# FeatherAzureSphere.net
KiCad netlist of a schematic drawn in EAGLE
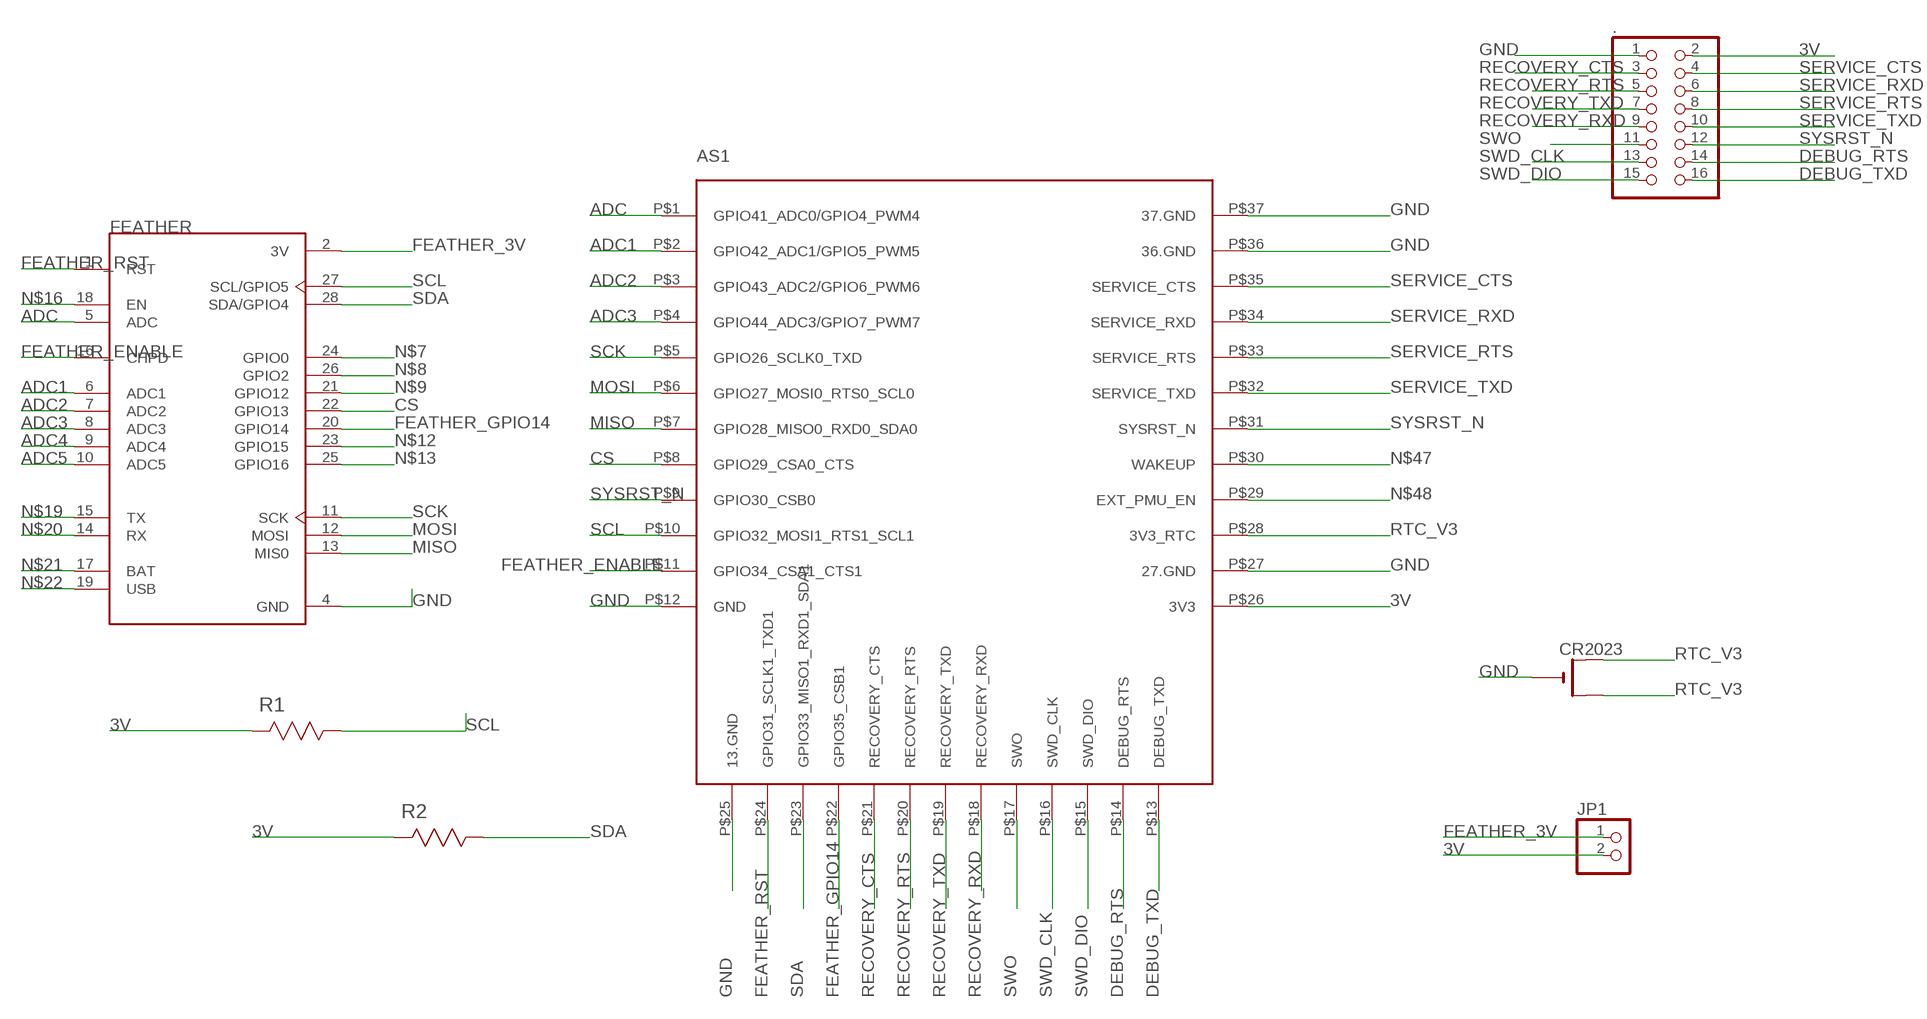
[diagram p0: schematic, sheet 1]

(export (version "E")
  (design (tool "Eeschema 10.0.6"))
  (components
    (comp (ref ".")
      (value "PINHD-2X8")
      (footprint "eagle-import:2X08")
      (libsource (lib "eagle-import") (part "PINHD-2X8"))
    )
    (comp (ref "AS1")
      (value "WF-M620-RSC1")
      (footprint "eagle-import:WF-M620-RSC1")
      (libsource (lib "eagle-import") (part "WF-M620-RSC1"))
    )
    (comp (ref "CR2023")
      (value "CR2032SMT")
      (footprint "eagle-import:CR2032-SMD")
      (libsource (lib "eagle-import") (part "CR2032SMT"))
    )
    (comp (ref "FEATHER")
      (value "2821")
      (footprint "eagle-import:XCVR_2821")
      (fields (field (name "MF") "Adafruit Industries"))
      (libsource (lib "eagle-import") (part "2821"))
    )
    (comp (ref "JP1")
      (value "PINHD-1X2")
      (footprint "eagle-import:1X02")
      (libsource (lib "eagle-import") (part "PINHD-1X2"))
    )
    (comp (ref "R1")
      (value "ERJ-8RQF1R5V")
      (footprint "eagle-import:RESC3216X71N")
      (fields (field (name "TOLERANCE") "±1 %"))
      (libsource (lib "eagle-import") (part "ERJ-8RQF1R5V"))
    )
    (comp (ref "R2")
      (value "ERJ-8RQF1R5V")
      (footprint "eagle-import:RESC3216X71N")
      (fields (field (name "TOLERANCE") "±1 %"))
      (libsource (lib "eagle-import") (part "ERJ-8RQF1R5V"))
    )
  )
  (nets
    (net (code "1") (name "/3V") (class "Default")
      (node (ref ".") (pin "2") (pinfunction "2_2") (pintype "passive"))
      (node (ref "AS1") (pin "P$26") (pinfunction "3V3_P$26") (pintype "bidirectional"))
      (node (ref "JP1") (pin "2") (pinfunction "2_2") (pintype "passive"))
      (node (ref "R1") (pin "2") (pinfunction "R2_2") (pintype "passive"))
      (node (ref "R2") (pin "2") (pinfunction "R2_2") (pintype "passive"))
    )
    (net (code "2") (name "/ADC") (class "Default")
      (node (ref "AS1") (pin "P$1") (pinfunction "GPIO41_ADC0/GPIO4_PWM4_P$1") (pintype "bidirectional"))
      (node (ref "FEATHER") (pin "5") (pinfunction "ADC_5") (pintype "bidirectional"))
    )
    (net (code "3") (name "/ADC1") (class "Default")
      (node (ref "AS1") (pin "P$2") (pinfunction "GPIO42_ADC1/GPIO5_PWM5_P$2") (pintype "bidirectional"))
      (node (ref "FEATHER") (pin "6") (pinfunction "ADC1_6") (pintype "bidirectional"))
    )
    (net (code "4") (name "/ADC2") (class "Default")
      (node (ref "AS1") (pin "P$3") (pinfunction "GPIO43_ADC2/GPIO6_PWM6_P$3") (pintype "bidirectional"))
      (node (ref "FEATHER") (pin "7") (pinfunction "ADC2_7") (pintype "bidirectional"))
    )
    (net (code "5") (name "/ADC3") (class "Default")
      (node (ref "AS1") (pin "P$4") (pinfunction "GPIO44_ADC3/GPIO7_PWM7_P$4") (pintype "bidirectional"))
      (node (ref "FEATHER") (pin "8") (pinfunction "ADC3_8") (pintype "bidirectional"))
    )
    (net (code "6") (name "/ADC4") (class "Default")
      (node (ref "FEATHER") (pin "9") (pinfunction "ADC4_9") (pintype "bidirectional"))
    )
    (net (code "7") (name "/ADC5") (class "Default")
      (node (ref "FEATHER") (pin "10") (pinfunction "ADC5_10") (pintype "bidirectional"))
    )
    (net (code "8") (name "/CS") (class "Default")
      (node (ref "AS1") (pin "P$8") (pinfunction "GPIO29_CSA0_CTS_P$8") (pintype "bidirectional"))
      (node (ref "FEATHER") (pin "22") (pinfunction "GPIO13_22") (pintype "bidirectional"))
    )
    (net (code "9") (name "/DEBUG_RTS") (class "Default")
      (node (ref ".") (pin "14") (pinfunction "14_14") (pintype "passive"))
      (node (ref "AS1") (pin "P$14") (pinfunction "DEBUG_RTS_P$14") (pintype "bidirectional"))
    )
    (net (code "10") (name "/DEBUG_TXD") (class "Default")
      (node (ref ".") (pin "16") (pinfunction "16_16") (pintype "passive"))
      (node (ref "AS1") (pin "P$13") (pinfunction "DEBUG_TXD_P$13") (pintype "bidirectional"))
    )
    (net (code "11") (name "/FEATHER_3V") (class "Default")
      (node (ref "FEATHER") (pin "2") (pinfunction "3V_2") (pintype "power_in"))
      (node (ref "JP1") (pin "1") (pinfunction "1_1") (pintype "passive"))
    )
    (net (code "12") (name "/FEATHER_ENABLE") (class "Default")
      (node (ref "AS1") (pin "P$11") (pinfunction "GPIO34_CSA1_CTS1_P$11") (pintype "bidirectional"))
      (node (ref "FEATHER") (pin "16") (pinfunction "CHPD_16") (pintype "bidirectional"))
    )
    (net (code "13") (name "/FEATHER_GPIO14") (class "Default")
      (node (ref "AS1") (pin "P$22") (pinfunction "GPIO35_CSB1_P$22") (pintype "bidirectional"))
      (node (ref "FEATHER") (pin "20") (pinfunction "GPIO14_20") (pintype "bidirectional"))
    )
    (net (code "14") (name "/FEATHER_RST") (class "Default")
      (node (ref "AS1") (pin "P$24") (pinfunction "GPIO31_SCLK1_TXD1_P$24") (pintype "bidirectional"))
      (node (ref "FEATHER") (pin "1") (pinfunction "RST_1") (pintype "input"))
    )
    (net (code "15") (name "/GND") (class "Default")
      (node (ref ".") (pin "1") (pinfunction "1_1") (pintype "passive"))
      (node (ref "AS1") (pin "P$12") (pinfunction "GND_P$12") (pintype "bidirectional"))
      (node (ref "AS1") (pin "P$25") (pinfunction "13.GND_P$25") (pintype "bidirectional"))
      (node (ref "AS1") (pin "P$27") (pinfunction "27.GND_P$27") (pintype "bidirectional"))
      (node (ref "AS1") (pin "P$36") (pinfunction "36.GND_P$36") (pintype "bidirectional"))
      (node (ref "AS1") (pin "P$37") (pinfunction "37.GND_P$37") (pintype "bidirectional"))
      (node (ref "CR2023") (pin "-") (pinfunction "-_-") (pintype "passive"))
      (node (ref "FEATHER") (pin "4") (pinfunction "GND_4") (pintype "power_in"))
    )
    (net (code "16") (name "/MISO") (class "Default")
      (node (ref "AS1") (pin "P$7") (pinfunction "GPIO28_MISO0_RXD0_SDA0_P$7") (pintype "bidirectional"))
      (node (ref "FEATHER") (pin "13") (pinfunction "MIS0_13") (pintype "input"))
    )
    (net (code "17") (name "/MOSI") (class "Default")
      (node (ref "AS1") (pin "P$6") (pinfunction "GPIO27_MOSI0_RTS0_SCL0_P$6") (pintype "bidirectional"))
      (node (ref "FEATHER") (pin "12") (pinfunction "MOSI_12") (pintype "output"))
    )
    (net (code "18") (name "/N$7") (class "Default")
      (node (ref "FEATHER") (pin "24") (pinfunction "GPIO0_24") (pintype "bidirectional"))
    )
    (net (code "19") (name "/N$8") (class "Default")
      (node (ref "FEATHER") (pin "26") (pinfunction "GPIO2_26") (pintype "bidirectional"))
    )
    (net (code "20") (name "/N$9") (class "Default")
      (node (ref "FEATHER") (pin "21") (pinfunction "GPIO12_21") (pintype "bidirectional"))
    )
    (net (code "21") (name "/N$12") (class "Default")
      (node (ref "FEATHER") (pin "23") (pinfunction "GPIO15_23") (pintype "bidirectional"))
    )
    (net (code "22") (name "/N$13") (class "Default")
      (node (ref "FEATHER") (pin "25") (pinfunction "GPIO16_25") (pintype "bidirectional"))
    )
    (net (code "23") (name "/N$16") (class "Default")
      (node (ref "FEATHER") (pin "18") (pinfunction "EN_18") (pintype "input"))
    )
    (net (code "24") (name "/N$19") (class "Default")
      (node (ref "FEATHER") (pin "15") (pinfunction "TX_15") (pintype "output"))
    )
    (net (code "25") (name "/N$20") (class "Default")
      (node (ref "FEATHER") (pin "14") (pinfunction "RX_14") (pintype "input"))
    )
    (net (code "26") (name "/N$21") (class "Default")
      (node (ref "FEATHER") (pin "17") (pinfunction "BAT_17") (pintype "bidirectional"))
    )
    (net (code "27") (name "/N$22") (class "Default")
      (node (ref "FEATHER") (pin "19") (pinfunction "USB_19") (pintype "bidirectional"))
    )
    (net (code "28") (name "/N$47") (class "Default")
      (node (ref "AS1") (pin "P$30") (pinfunction "WAKEUP_P$30") (pintype "bidirectional"))
    )
    (net (code "29") (name "/N$48") (class "Default")
      (node (ref "AS1") (pin "P$29") (pinfunction "EXT_PMU_EN_P$29") (pintype "bidirectional"))
    )
    (net (code "30") (name "/RECOVERY_CTS") (class "Default")
      (node (ref ".") (pin "3") (pinfunction "3_3") (pintype "passive"))
      (node (ref "AS1") (pin "P$21") (pinfunction "RECOVERY_CTS_P$21") (pintype "bidirectional"))
    )
    (net (code "31") (name "/RECOVERY_RTS") (class "Default")
      (node (ref ".") (pin "5") (pinfunction "5_5") (pintype "passive"))
      (node (ref "AS1") (pin "P$20") (pinfunction "RECOVERY_RTS_P$20") (pintype "bidirectional"))
    )
    (net (code "32") (name "/RECOVERY_RXD") (class "Default")
      (node (ref ".") (pin "9") (pinfunction "9_9") (pintype "passive"))
      (node (ref "AS1") (pin "P$18") (pinfunction "RECOVERY_RXD_P$18") (pintype "bidirectional"))
    )
    (net (code "33") (name "/RECOVERY_TXD") (class "Default")
      (node (ref ".") (pin "7") (pinfunction "7_7") (pintype "passive"))
      (node (ref "AS1") (pin "P$19") (pinfunction "RECOVERY_TXD_P$19") (pintype "bidirectional"))
    )
    (net (code "34") (name "/RTC_V3") (class "Default")
      (node (ref "AS1") (pin "P$28") (pinfunction "3V3_RTC_P$28") (pintype "bidirectional"))
      (node (ref "CR2023") (pin "+$1") (pinfunction "+_+$1") (pintype "passive"))
      (node (ref "CR2023") (pin "+$2") (pinfunction "+1_+$2") (pintype "passive"))
    )
    (net (code "35") (name "/SCK") (class "Default")
      (node (ref "AS1") (pin "P$5") (pinfunction "GPIO26_SCLK0_TXD_P$5") (pintype "bidirectional"))
      (node (ref "FEATHER") (pin "11") (pinfunction "SCK_11") (pintype "bidirectional"))
    )
    (net (code "36") (name "/SCL") (class "Default")
      (node (ref "AS1") (pin "P$10") (pinfunction "GPIO32_MOSI1_RTS1_SCL1_P$10") (pintype "bidirectional"))
      (node (ref "FEATHER") (pin "27") (pinfunction "SCL/GPIO5_27") (pintype "bidirectional"))
      (node (ref "R1") (pin "1") (pinfunction "R1_1") (pintype "passive"))
    )
    (net (code "37") (name "/SDA") (class "Default")
      (node (ref "AS1") (pin "P$23") (pinfunction "GPIO33_MISO1_RXD1_SDA1_P$23") (pintype "bidirectional"))
      (node (ref "FEATHER") (pin "28") (pinfunction "SDA/GPIO4_28") (pintype "bidirectional"))
      (node (ref "R2") (pin "1") (pinfunction "R1_1") (pintype "passive"))
    )
    (net (code "38") (name "/SERVICE_CTS") (class "Default")
      (node (ref ".") (pin "4") (pinfunction "4_4") (pintype "passive"))
      (node (ref "AS1") (pin "P$35") (pinfunction "SERVICE_CTS_P$35") (pintype "bidirectional"))
    )
    (net (code "39") (name "/SERVICE_RTS") (class "Default")
      (node (ref ".") (pin "8") (pinfunction "8_8") (pintype "passive"))
      (node (ref "AS1") (pin "P$33") (pinfunction "SERVICE_RTS_P$33") (pintype "bidirectional"))
    )
    (net (code "40") (name "/SERVICE_RXD") (class "Default")
      (node (ref ".") (pin "6") (pinfunction "6_6") (pintype "passive"))
      (node (ref "AS1") (pin "P$34") (pinfunction "SERVICE_RXD_P$34") (pintype "bidirectional"))
    )
    (net (code "41") (name "/SERVICE_TXD") (class "Default")
      (node (ref ".") (pin "10") (pinfunction "10_10") (pintype "passive"))
      (node (ref "AS1") (pin "P$32") (pinfunction "SERVICE_TXD_P$32") (pintype "bidirectional"))
    )
    (net (code "42") (name "/SWD_CLK") (class "Default")
      (node (ref ".") (pin "13") (pinfunction "13_13") (pintype "passive"))
      (node (ref "AS1") (pin "P$16") (pinfunction "SWD_CLK_P$16") (pintype "bidirectional"))
    )
    (net (code "43") (name "/SWD_DIO") (class "Default")
      (node (ref ".") (pin "15") (pinfunction "15_15") (pintype "passive"))
      (node (ref "AS1") (pin "P$15") (pinfunction "SWD_DIO_P$15") (pintype "bidirectional"))
    )
    (net (code "44") (name "/SWO") (class "Default")
      (node (ref ".") (pin "11") (pinfunction "11_11") (pintype "passive"))
      (node (ref "AS1") (pin "P$17") (pinfunction "SWO_P$17") (pintype "bidirectional"))
    )
    (net (code "45") (name "/SYSRST_N") (class "Default")
      (node (ref ".") (pin "12") (pinfunction "12_12") (pintype "passive"))
      (node (ref "AS1") (pin "P$31") (pinfunction "SYSRST_N_P$31") (pintype "bidirectional"))
      (node (ref "AS1") (pin "P$9") (pinfunction "GPIO30_CSB0_P$9") (pintype "bidirectional"))
    )
  )
)
